# devboard.net
KiCad netlist of a schematic drawn in EAGLE
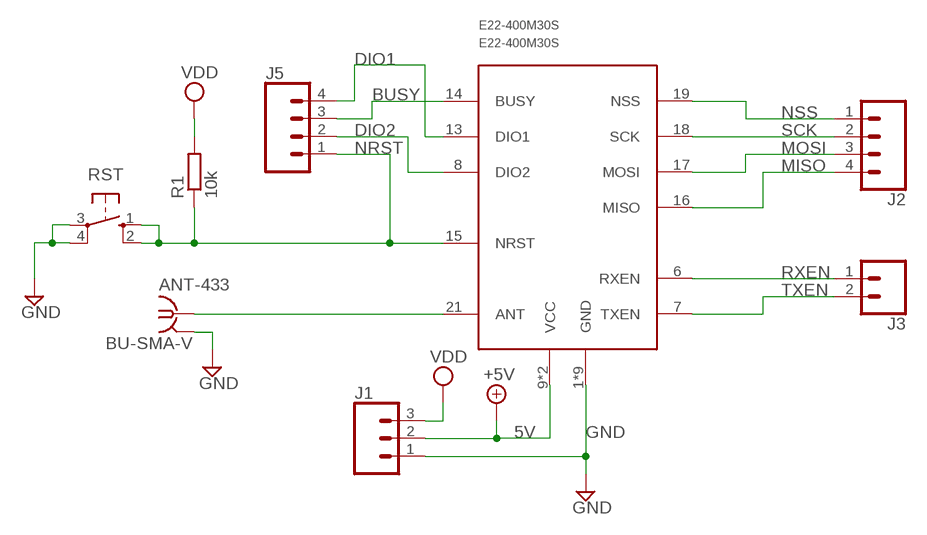
[diagram p0: schematic, sheet 1]

(export (version "E")
  (design (tool "Eeschema 10.0.6"))
  (components
    (comp (ref "ANT-433")
      (value "BU-SMA-V")
      (footprint "eagle-import:BU-SMA-V")
      (libsource (lib "eagle-import") (part "BU-SMA-V"))
    )
    (comp (ref "E22-400M30S")
      (value "E22-400M30S")
      (footprint "eagle-import:E22-400M30S")
      (libsource (lib "eagle-import") (part "E22-400M30S"))
    )
    (comp (ref "J1")
      (value "CONN_03LOCK_LONGPADS")
      (footprint "eagle-import:1X03_LOCK_LONGPADS")
      (libsource (lib "eagle-import") (part "CONN_03LOCK_LONGPADS"))
    )
    (comp (ref "J2")
      (value "CONN_04LOCK_LONGPADS")
      (footprint "eagle-import:1X04_LOCK_LONGPADS")
      (libsource (lib "eagle-import") (part "CONN_04LOCK_LONGPADS"))
    )
    (comp (ref "J3")
      (value "CONN_02PTH3")
      (footprint "eagle-import:1X02_LONGPADS")
      (libsource (lib "eagle-import") (part "CONN_02PTH3"))
    )
    (comp (ref "J5")
      (value "CONN_04LOCK_LONGPADS")
      (footprint "eagle-import:1X04_LOCK_LONGPADS")
      (libsource (lib "eagle-import") (part "CONN_04LOCK_LONGPADS"))
    )
    (comp (ref "R1")
      (value "10k")
      (footprint "eagle-import:R0603")
      (libsource (lib "eagle-import") (part "R-EU_R0603"))
    )
    (comp (ref "RST")
      (value "10-XX")
      (footprint "eagle-import:B3F-10XX")
      (fields (field (name "MPN") "B3F-1000"))
      (libsource (lib "eagle-import") (part "10-XX"))
    )
  )
  (nets
    (net (code "1") (name "+5V") (class "Default")
      (node (ref "E22-400M30S") (pin "10") (pinfunction "VCC_10") (pintype "power_in"))
      (node (ref "E22-400M30S") (pin "9") (pinfunction "VCC_9") (pintype "power_in"))
      (node (ref "J1") (pin "2") (pinfunction "2_2") (pintype "passive"))
    )
    (net (code "2") (name "/BUSY") (class "Default")
      (node (ref "E22-400M30S") (pin "14") (pinfunction "BUSY_14") (pintype "output"))
      (node (ref "J5") (pin "3") (pinfunction "3_3") (pintype "passive"))
    )
    (net (code "3") (name "/DIO1") (class "Default")
      (node (ref "E22-400M30S") (pin "13") (pinfunction "DIO1_13") (pintype "bidirectional"))
      (node (ref "J5") (pin "4") (pinfunction "4_4") (pintype "passive"))
    )
    (net (code "4") (name "/DIO2") (class "Default")
      (node (ref "E22-400M30S") (pin "8") (pinfunction "DIO2_8") (pintype "bidirectional"))
      (node (ref "J5") (pin "2") (pinfunction "2_2") (pintype "passive"))
    )
    (net (code "5") (name "/MISO") (class "Default")
      (node (ref "E22-400M30S") (pin "16") (pinfunction "MISO_16") (pintype "output"))
      (node (ref "J2") (pin "4") (pinfunction "4_4") (pintype "passive"))
    )
    (net (code "6") (name "/MOSI") (class "Default")
      (node (ref "E22-400M30S") (pin "17") (pinfunction "MOSI_17") (pintype "input"))
      (node (ref "J2") (pin "3") (pinfunction "3_3") (pintype "passive"))
    )
    (net (code "7") (name "/NRST") (class "Default")
      (node (ref "E22-400M30S") (pin "15") (pinfunction "NRST_15") (pintype "input"))
      (node (ref "J5") (pin "1") (pinfunction "1_1") (pintype "passive"))
      (node (ref "R1") (pin "1") (pinfunction "1_1") (pintype "passive"))
      (node (ref "RST") (pin "1") (pinfunction "S_1") (pintype "passive"))
      (node (ref "RST") (pin "2") (pinfunction "S1_2") (pintype "passive"))
    )
    (net (code "8") (name "/NSS") (class "Default")
      (node (ref "E22-400M30S") (pin "19") (pinfunction "NSS_19") (pintype "input"))
      (node (ref "J2") (pin "1") (pinfunction "1_1") (pintype "passive"))
    )
    (net (code "9") (name "/RXEN") (class "Default")
      (node (ref "E22-400M30S") (pin "6") (pinfunction "RXEN_6") (pintype "input"))
      (node (ref "J3") (pin "1") (pinfunction "1_1") (pintype "passive"))
    )
    (net (code "10") (name "/SCK") (class "Default")
      (node (ref "E22-400M30S") (pin "18") (pinfunction "SCK_18") (pintype "input"))
      (node (ref "J2") (pin "2") (pinfunction "2_2") (pintype "passive"))
    )
    (net (code "11") (name "/TXEN") (class "Default")
      (node (ref "E22-400M30S") (pin "7") (pinfunction "TXEN_7") (pintype "input"))
      (node (ref "J3") (pin "2") (pinfunction "2_2") (pintype "passive"))
    )
    (net (code "12") (name "GND") (class "Default")
      (node (ref "ANT-433") (pin "2") (pinfunction "2_2") (pintype "passive"))
      (node (ref "ANT-433") (pin "3") (pinfunction "2_3") (pintype "passive"))
      (node (ref "ANT-433") (pin "4") (pinfunction "2_4") (pintype "passive"))
      (node (ref "ANT-433") (pin "5") (pinfunction "2_5") (pintype "passive"))
      (node (ref "E22-400M30S") (pin "1") (pinfunction "GND_1") (pintype "power_in"))
      (node (ref "E22-400M30S") (pin "11") (pinfunction "GND_11") (pintype "power_in"))
      (node (ref "E22-400M30S") (pin "12") (pinfunction "GND_12") (pintype "power_in"))
      (node (ref "E22-400M30S") (pin "2") (pinfunction "GND_2") (pintype "power_in"))
      (node (ref "E22-400M30S") (pin "20") (pinfunction "GND_20") (pintype "power_in"))
      (node (ref "E22-400M30S") (pin "22") (pinfunction "GND_22") (pintype "power_in"))
      (node (ref "E22-400M30S") (pin "3") (pinfunction "GND_3") (pintype "power_in"))
      (node (ref "E22-400M30S") (pin "4") (pinfunction "GND_4") (pintype "power_in"))
      (node (ref "E22-400M30S") (pin "5") (pinfunction "GND_5") (pintype "power_in"))
      (node (ref "J1") (pin "1") (pinfunction "1_1") (pintype "passive"))
      (node (ref "RST") (pin "3") (pinfunction "P_3") (pintype "passive"))
      (node (ref "RST") (pin "4") (pinfunction "P1_4") (pintype "passive"))
    )
    (net (code "13") (name "Net-(E22-400M30S-ANT)") (class "Default")
      (node (ref "ANT-433") (pin "1") (pinfunction "1_1") (pintype "passive"))
      (node (ref "E22-400M30S") (pin "21") (pinfunction "ANT_21") (pintype "output"))
    )
    (net (code "14") (name "VDD") (class "Default")
      (node (ref "J1") (pin "3") (pinfunction "3_3") (pintype "passive"))
      (node (ref "R1") (pin "2") (pinfunction "2_2") (pintype "passive"))
    )
  )
)
